# final.net
KiCad netlist of a schematic drawn in EAGLE
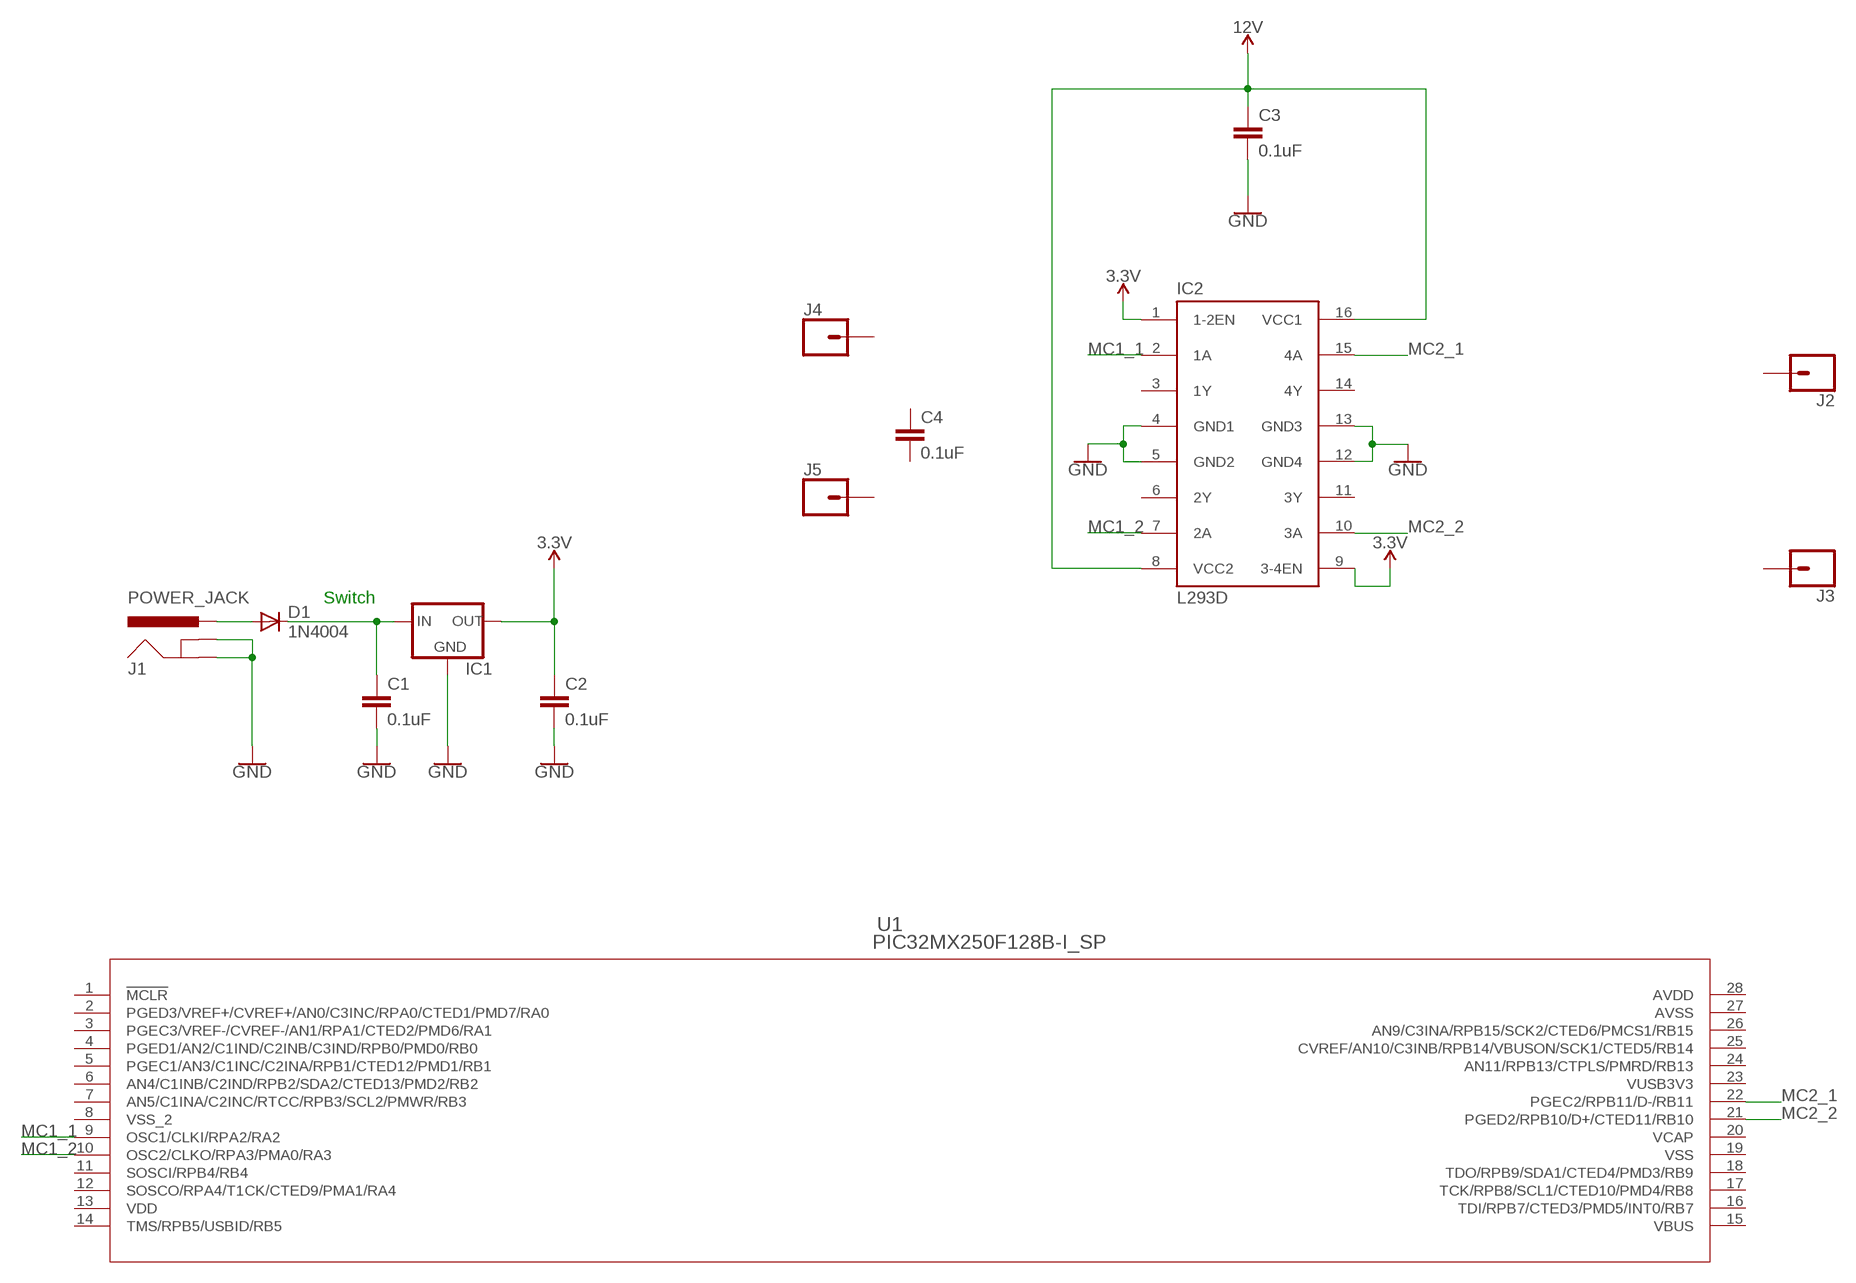
[diagram p0: schematic, sheet 1]

(export (version "E")
  (design (tool "Eeschema 10.0.6"))
  (components
    (comp (ref "C1")
      (value "0.1uF")
      (footprint "eagle-import:0402")
      (libsource (lib "eagle-import") (part "0.1UF-0402-16V-10%"))
    )
    (comp (ref "C2")
      (value "0.1uF")
      (footprint "eagle-import:0402")
      (libsource (lib "eagle-import") (part "0.1UF-0402-16V-10%"))
    )
    (comp (ref "C3")
      (value "0.1uF")
      (footprint "eagle-import:0402")
      (libsource (lib "eagle-import") (part "0.1UF-0402-16V-10%"))
    )
    (comp (ref "C4")
      (value "0.1uF")
      (footprint "eagle-import:0402")
      (libsource (lib "eagle-import") (part "0.1UF-0402-16V-10%"))
    )
    (comp (ref "D1")
      (value "1N4004")
      (footprint "eagle-import:DO41-10")
      (libsource (lib "eagle-import") (part "1N4004"))
    )
    (comp (ref "IC1")
      (value "MCP1700INLINE")
      (footprint "eagle-import:TO92-INLINE")
      (libsource (lib "eagle-import") (part "MCP1700INLINE"))
    )
    (comp (ref "IC2")
      (value "L293D")
      (footprint "eagle-import:DIL16")
      (libsource (lib "eagle-import") (part "L293D"))
    )
    (comp (ref "J1")
      (value "POWER_JACK")
      (footprint "eagle-import:POWER_JACK_PTH")
      (libsource (lib "eagle-import") (part "POWER_JACK"))
    )
    (comp (ref "J2")
      (value "CONN_01")
      (footprint "eagle-import:1X01")
      (libsource (lib "eagle-import") (part "CONN_01"))
    )
    (comp (ref "J3")
      (value "CONN_01")
      (footprint "eagle-import:1X01")
      (libsource (lib "eagle-import") (part "CONN_01"))
    )
    (comp (ref "J4")
      (value "CONN_01")
      (footprint "eagle-import:1X01")
      (libsource (lib "eagle-import") (part "CONN_01"))
    )
    (comp (ref "J5")
      (value "CONN_01")
      (footprint "eagle-import:1X01")
      (libsource (lib "eagle-import") (part "CONN_01"))
    )
    (comp (ref "U1")
      (value "PIC32MX250F128B-I_SP")
      (footprint "eagle-import:SPDIP28_300MC")
      (libsource (lib "eagle-import") (part "PIC32MX250F128B-I_SP"))
    )
  )
  (nets
    (net (code "1") (name "/AVDD") (class "Default")
      (node (ref "U1") (pin "28") (pinfunction "AVDD_28") (pintype "power_in"))
    )
    (net (code "2") (name "/AVSS") (class "Default")
      (node (ref "U1") (pin "27") (pinfunction "AVSS_27") (pintype "power_in"))
    )
    (net (code "3") (name "/MC1_1") (class "Default")
      (node (ref "IC2") (pin "2") (pinfunction "1A_2") (pintype "input"))
      (node (ref "U1") (pin "9") (pinfunction "OSC1/CLKI/RPA2/RA2_9") (pintype "bidirectional"))
    )
    (net (code "4") (name "/MC1_2") (class "Default")
      (node (ref "IC2") (pin "7") (pinfunction "2A_7") (pintype "input"))
      (node (ref "U1") (pin "10") (pinfunction "OSC2/CLKO/RPA3/PMA0/RA3_10") (pintype "bidirectional"))
    )
    (net (code "5") (name "/MC2_1") (class "Default")
      (node (ref "IC2") (pin "15") (pinfunction "4A_15") (pintype "input"))
      (node (ref "U1") (pin "22") (pinfunction "PGEC2/RPB11/D-/RB11_22") (pintype "bidirectional"))
    )
    (net (code "6") (name "/MC2_2") (class "Default")
      (node (ref "IC2") (pin "10") (pinfunction "3A_10") (pintype "input"))
      (node (ref "U1") (pin "21") (pinfunction "PGED2/RPB10/D+/CTED11/RB10_21") (pintype "bidirectional"))
    )
    (net (code "7") (name "/VBUS") (class "Default")
      (node (ref "U1") (pin "15") (pinfunction "VBUS_15") (pintype "power_in"))
    )
    (net (code "8") (name "/VCAP") (class "Default")
      (node (ref "U1") (pin "20") (pinfunction "VCAP_20") (pintype "power_in"))
    )
    (net (code "9") (name "/VDD") (class "Default")
      (node (ref "U1") (pin "13") (pinfunction "VDD_13") (pintype "power_in"))
    )
    (net (code "10") (name "/VSS") (class "Default")
      (node (ref "U1") (pin "19") (pinfunction "VSS_19") (pintype "power_in"))
    )
    (net (code "11") (name "/VSS_2") (class "Default")
      (node (ref "U1") (pin "8") (pinfunction "VSS_2_8") (pintype "power_in"))
    )
    (net (code "12") (name "/VUSB3V3") (class "Default")
      (node (ref "U1") (pin "23") (pinfunction "VUSB3V3_23") (pintype "power_in"))
    )
    (net (code "13") (name "3.3V") (class "Default")
      (node (ref "C2") (pin "1") (pinfunction "1_1") (pintype "passive"))
      (node (ref "IC1") (pin "3") (pinfunction "OUT_3") (pintype "passive"))
      (node (ref "IC2") (pin "1") (pinfunction "1-2EN_1") (pintype "input"))
      (node (ref "IC2") (pin "9") (pinfunction "3-4EN_9") (pintype "input"))
    )
    (net (code "14") (name "12V") (class "Default")
      (node (ref "C3") (pin "1") (pinfunction "1_1") (pintype "passive"))
      (node (ref "IC2") (pin "16") (pinfunction "VCC1_16") (pintype "power_in"))
      (node (ref "IC2") (pin "8") (pinfunction "VCC2_8") (pintype "power_in"))
    )
    (net (code "15") (name "GND") (class "Default")
      (node (ref "C1") (pin "2") (pinfunction "2_2") (pintype "passive"))
      (node (ref "C2") (pin "2") (pinfunction "2_2") (pintype "passive"))
      (node (ref "C3") (pin "2") (pinfunction "2_2") (pintype "passive"))
      (node (ref "IC1") (pin "1") (pinfunction "GND_1") (pintype "input"))
      (node (ref "IC2") (pin "12") (pinfunction "GND4_12") (pintype "power_in"))
      (node (ref "IC2") (pin "13") (pinfunction "GND3_13") (pintype "power_in"))
      (node (ref "IC2") (pin "4") (pinfunction "GND1_4") (pintype "power_in"))
      (node (ref "IC2") (pin "5") (pinfunction "GND2_5") (pintype "power_in"))
      (node (ref "J1") (pin "GND") (pinfunction "GND_GND") (pintype "bidirectional"))
      (node (ref "J1") (pin "GNDBREAK") (pinfunction "GNDBREAK_GNDBREAK") (pintype "bidirectional"))
    )
    (net (code "16") (name "Net-(D1-PadA)") (class "Default")
      (node (ref "D1") (pin "A") (pinfunction "A_A") (pintype "passive"))
      (node (ref "J1") (pin "PWR") (pinfunction "PWR_PWR") (pintype "bidirectional"))
    )
    (net (code "17") (name "Net-(IC1-IN)") (class "Default")
      (node (ref "C1") (pin "1") (pinfunction "1_1") (pintype "passive"))
      (node (ref "D1") (pin "C") (pinfunction "C_C") (pintype "passive"))
      (node (ref "IC1") (pin "2") (pinfunction "IN_2") (pintype "input"))
    )
    (net (code "18") (name "unconnected-(C4-Pad1)") (class "Default")
      (node (ref "C4") (pin "1") (pinfunction "1_1") (pintype "passive"))
    )
    (net (code "19") (name "unconnected-(C4-Pad2)") (class "Default")
      (node (ref "C4") (pin "2") (pinfunction "2_2") (pintype "passive"))
    )
    (net (code "20") (name "unconnected-(IC2-1Y-Pad3)") (class "Default")
      (node (ref "IC2") (pin "3") (pinfunction "1Y_3") (pintype "output"))
    )
    (net (code "21") (name "unconnected-(IC2-2Y-Pad6)") (class "Default")
      (node (ref "IC2") (pin "6") (pinfunction "2Y_6") (pintype "output"))
    )
    (net (code "22") (name "unconnected-(IC2-3Y-Pad11)") (class "Default")
      (node (ref "IC2") (pin "11") (pinfunction "3Y_11") (pintype "output"))
    )
    (net (code "23") (name "unconnected-(IC2-4Y-Pad14)") (class "Default")
      (node (ref "IC2") (pin "14") (pinfunction "4Y_14") (pintype "output"))
    )
    (net (code "24") (name "unconnected-(J2-Pad1)") (class "Default")
      (node (ref "J2") (pin "1") (pinfunction "1_1") (pintype "passive"))
    )
    (net (code "25") (name "unconnected-(J3-Pad1)") (class "Default")
      (node (ref "J3") (pin "1") (pinfunction "1_1") (pintype "passive"))
    )
    (net (code "26") (name "unconnected-(J4-Pad1)") (class "Default")
      (node (ref "J4") (pin "1") (pinfunction "1_1") (pintype "passive"))
    )
    (net (code "27") (name "unconnected-(J5-Pad1)") (class "Default")
      (node (ref "J5") (pin "1") (pinfunction "1_1") (pintype "passive"))
    )
    (net (code "28") (name "unconnected-(U1-AN4{slash}C1INB{slash}C2IND{slash}RPB2{slash}SDA2{slash}CTED13{slash}PMD2{slash}RB2-Pad6)") (class "Default")
      (node (ref "U1") (pin "6") (pinfunction "AN4/C1INB/C2IND/RPB2/SDA2/CTED13/PMD2/RB2_6") (pintype "bidirectional"))
    )
    (net (code "29") (name "unconnected-(U1-AN5{slash}C1INA{slash}C2INC{slash}RTCC{slash}RPB3{slash}SCL2{slash}PMWR{slash}RB3-Pad7)") (class "Default")
      (node (ref "U1") (pin "7") (pinfunction "AN5/C1INA/C2INC/RTCC/RPB3/SCL2/PMWR/RB3_7") (pintype "bidirectional"))
    )
    (net (code "30") (name "unconnected-(U1-AN9{slash}C3INA{slash}RPB15{slash}SCK2{slash}CTED6{slash}PMCS1{slash}RB15-Pad26)") (class "Default")
      (node (ref "U1") (pin "26") (pinfunction "AN9/C3INA/RPB15/SCK2/CTED6/PMCS1/RB15_26") (pintype "bidirectional"))
    )
    (net (code "31") (name "unconnected-(U1-AN11{slash}RPB13{slash}CTPLS{slash}PMRD{slash}RB13-Pad24)") (class "Default")
      (node (ref "U1") (pin "24") (pinfunction "AN11/RPB13/CTPLS/PMRD/RB13_24") (pintype "bidirectional"))
    )
    (net (code "32") (name "unconnected-(U1-CVREF{slash}AN10{slash}C3INB{slash}RPB14{slash}VBUSON{slash}SCK1{slash}CTED5{slash}RB14-Pad25)") (class "Default")
      (node (ref "U1") (pin "25") (pinfunction "CVREF/AN10/C3INB/RPB14/VBUSON/SCK1/CTED5/RB14_25") (pintype "bidirectional"))
    )
    (net (code "33") (name "unconnected-(U1-PGEC1{slash}AN3{slash}C1INC{slash}C2INA{slash}RPB1{slash}CTED12{slash}PMD1{slash}RB1-Pad5)") (class "Default")
      (node (ref "U1") (pin "5") (pinfunction "PGEC1/AN3/C1INC/C2INA/RPB1/CTED12/PMD1/RB1_5") (pintype "bidirectional"))
    )
    (net (code "34") (name "unconnected-(U1-PGEC3{slash}VREF-{slash}CVREF-{slash}AN1{slash}RPA1{slash}CTED2{slash}PMD6{slash}RA1-Pad3)") (class "Default")
      (node (ref "U1") (pin "3") (pinfunction "PGEC3/VREF-/CVREF-/AN1/RPA1/CTED2/PMD6/RA1_3") (pintype "bidirectional"))
    )
    (net (code "35") (name "unconnected-(U1-PGED1{slash}AN2{slash}C1IND{slash}C2INB{slash}C3IND{slash}RPB0{slash}PMD0{slash}RB0-Pad4)") (class "Default")
      (node (ref "U1") (pin "4") (pinfunction "PGED1/AN2/C1IND/C2INB/C3IND/RPB0/PMD0/RB0_4") (pintype "bidirectional"))
    )
    (net (code "36") (name "unconnected-(U1-PGED3{slash}VREF+{slash}CVREF+{slash}AN0{slash}C3INC{slash}RPA0{slash}CTED1{slash}PMD7{slash}RA0-Pad2)") (class "Default")
      (node (ref "U1") (pin "2") (pinfunction "PGED3/VREF+/CVREF+/AN0/C3INC/RPA0/CTED1/PMD7/RA0_2") (pintype "bidirectional"))
    )
    (net (code "37") (name "unconnected-(U1-SOSCI{slash}RPB4{slash}RB4-Pad11)") (class "Default")
      (node (ref "U1") (pin "11") (pinfunction "SOSCI/RPB4/RB4_11") (pintype "bidirectional"))
    )
    (net (code "38") (name "unconnected-(U1-SOSCO{slash}RPA4{slash}T1CK{slash}CTED9{slash}PMA1{slash}RA4-Pad12)") (class "Default")
      (node (ref "U1") (pin "12") (pinfunction "SOSCO/RPA4/T1CK/CTED9/PMA1/RA4_12") (pintype "bidirectional"))
    )
    (net (code "39") (name "unconnected-(U1-TCK{slash}RPB8{slash}SCL1{slash}CTED10{slash}PMD4{slash}RB8-Pad17)") (class "Default")
      (node (ref "U1") (pin "17") (pinfunction "TCK/RPB8/SCL1/CTED10/PMD4/RB8_17") (pintype "bidirectional"))
    )
    (net (code "40") (name "unconnected-(U1-TDI{slash}RPB7{slash}CTED3{slash}PMD5{slash}INT0{slash}RB7-Pad16)") (class "Default")
      (node (ref "U1") (pin "16") (pinfunction "TDI/RPB7/CTED3/PMD5/INT0/RB7_16") (pintype "bidirectional"))
    )
    (net (code "41") (name "unconnected-(U1-TDO{slash}RPB9{slash}SDA1{slash}CTED4{slash}PMD3{slash}RB9-Pad18)") (class "Default")
      (node (ref "U1") (pin "18") (pinfunction "TDO/RPB9/SDA1/CTED4/PMD3/RB9_18") (pintype "bidirectional"))
    )
    (net (code "42") (name "unconnected-(U1-TMS{slash}RPB5{slash}USBID{slash}RB5-Pad14)") (class "Default")
      (node (ref "U1") (pin "14") (pinfunction "TMS/RPB5/USBID/RB5_14") (pintype "bidirectional"))
    )
    (net (code "43") (name "unconnected-(U1-~{MCLR}-Pad1)") (class "Default")
      (node (ref "U1") (pin "1") (pinfunction "~{MCLR}_1") (pintype "input"))
    )
  )
)
